# SCH_Octacon_Pots_Leds.net
KiCad netlist of a schematic drawn in EasyEDA
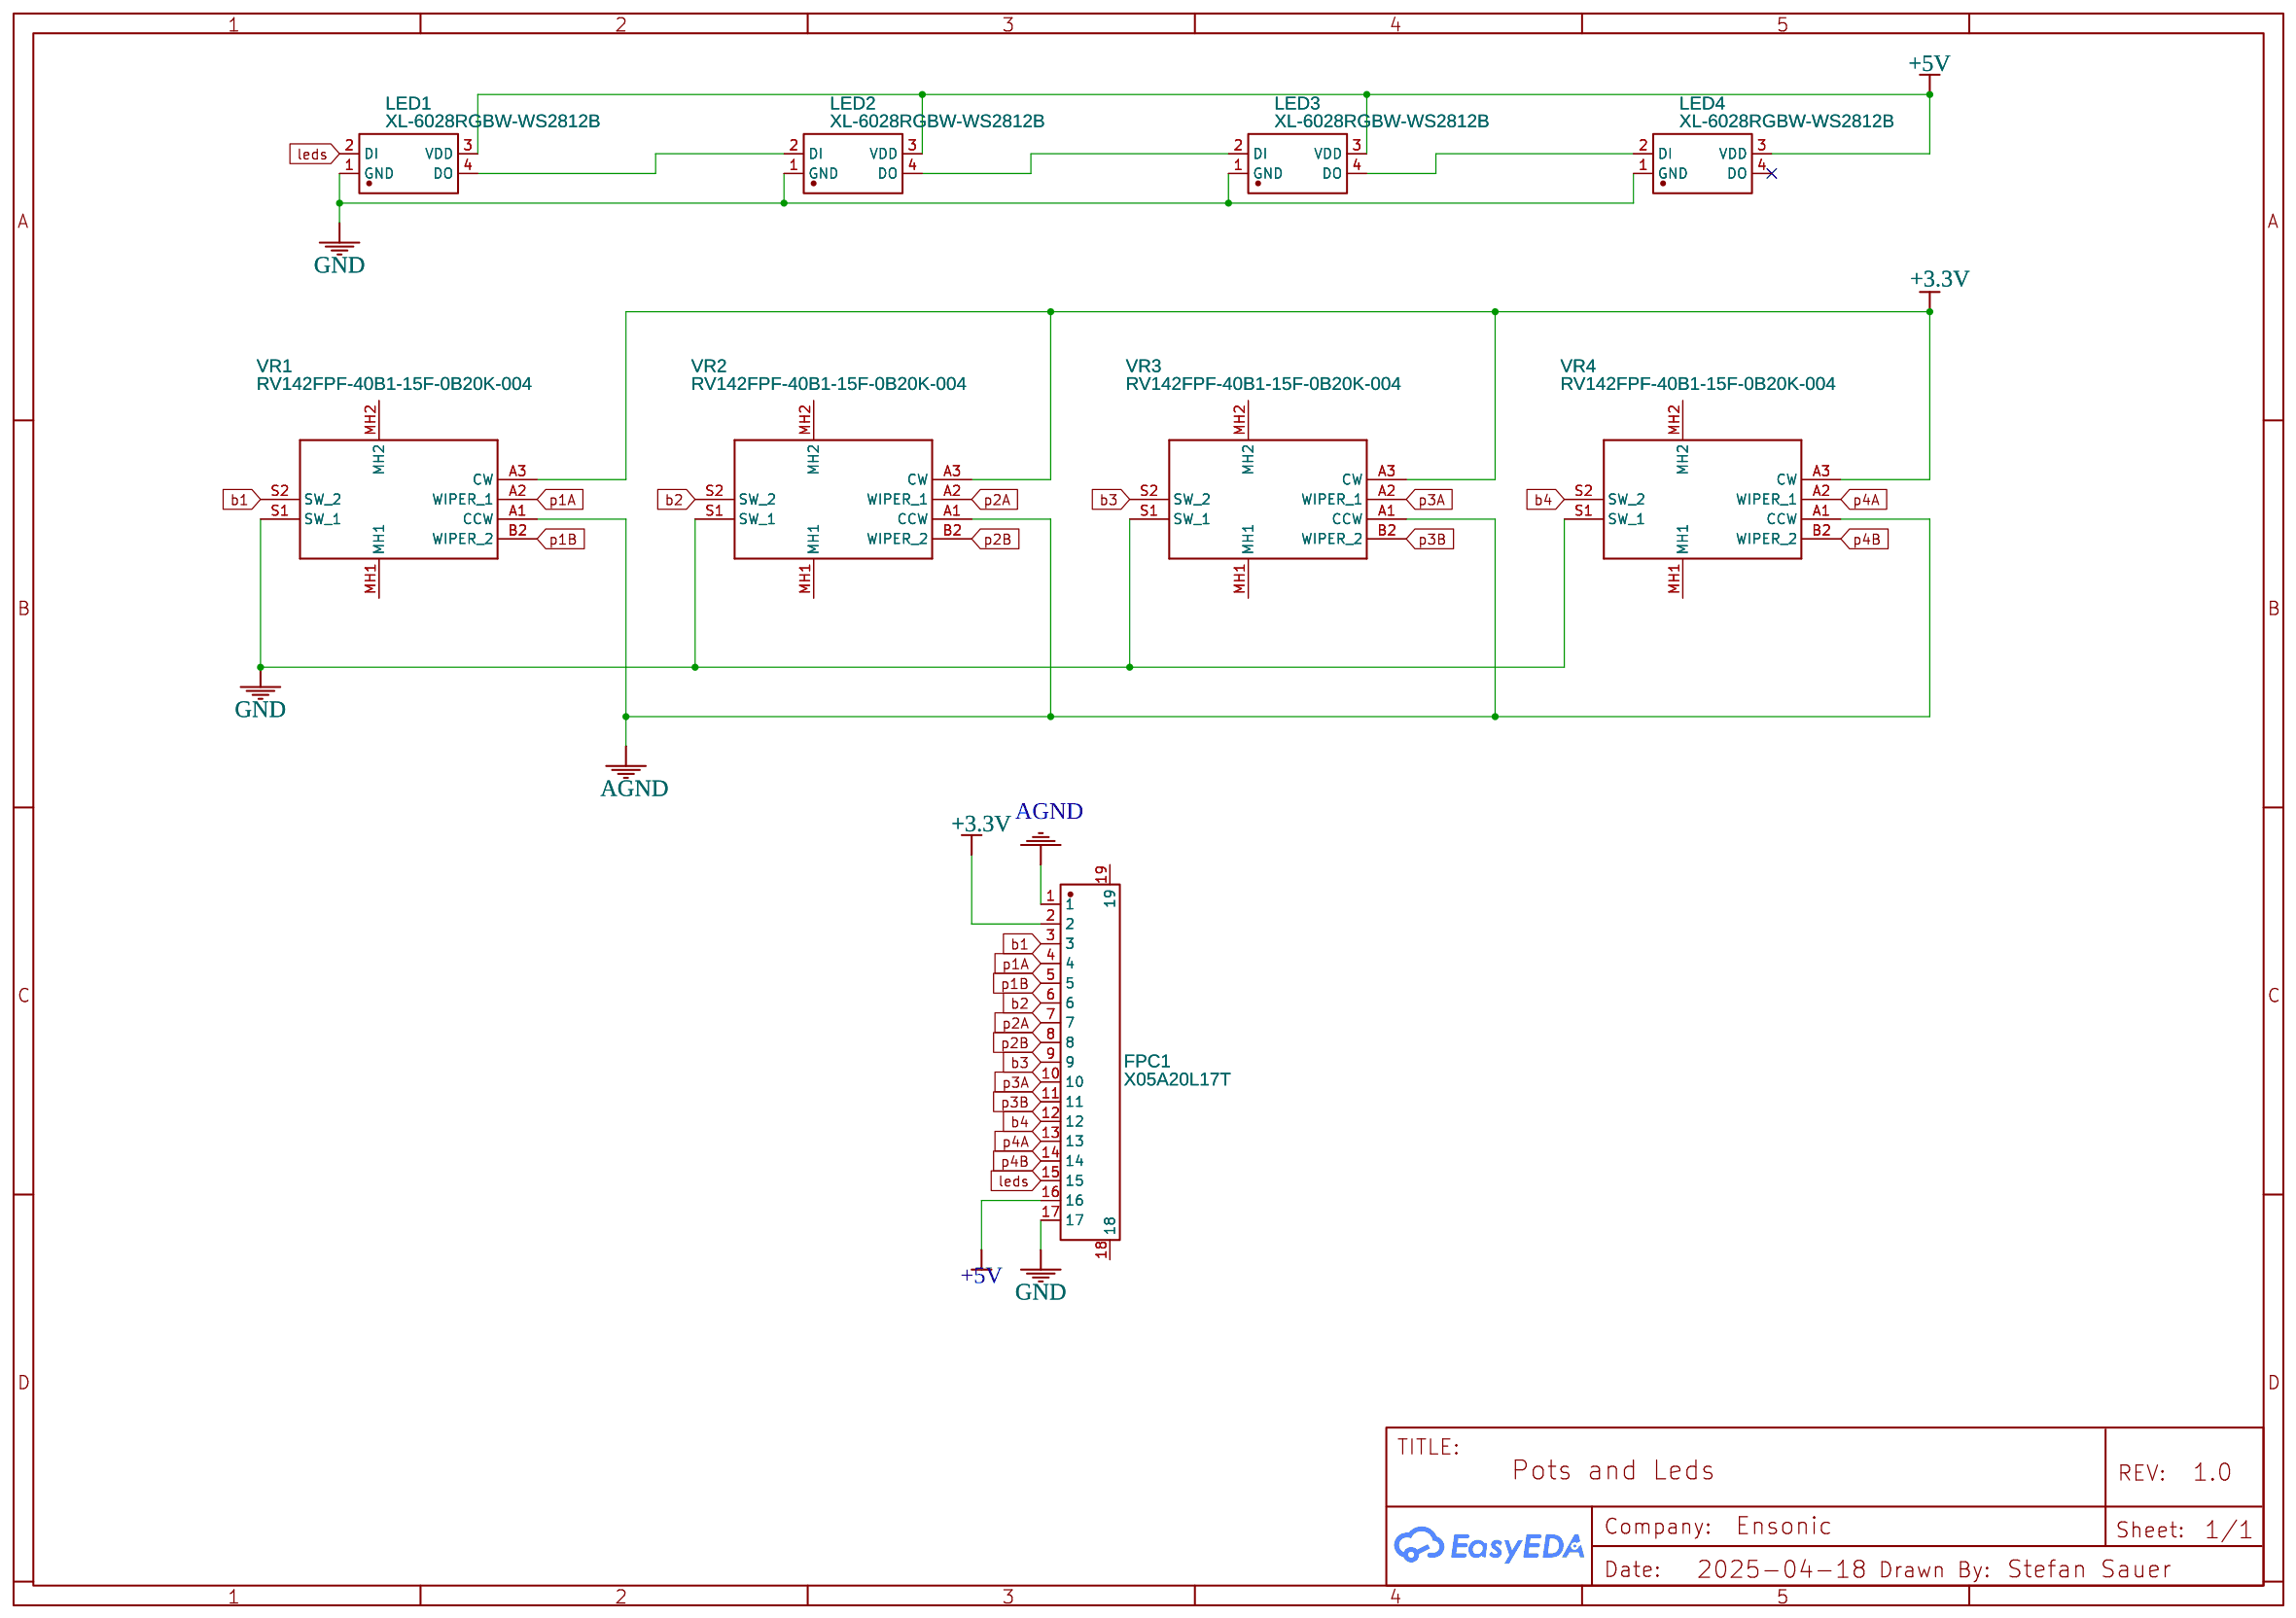
[diagram p0: schematic sheet]

(export (version "E")
  (design (tool "Eeschema 10.0.6"))
  (components
    (comp (ref "FPC1")
      (value "X05A20L17T")
      (fields (field (name "Manufacturer") "XKB Connection(中国星坤)"))
      (libsource (lib "") (part "X05A20L17T"))
    )
    (comp (ref "LED1")
      (value "XL-6028RGBW-WS2812B")
      (fields (field (name "Manufacturer") "XINGLIGHT(成兴光)"))
      (libsource (lib "") (part "XL-6028RGBW-WS2812B"))
    )
    (comp (ref "LED2")
      (value "XL-6028RGBW-WS2812B")
      (fields (field (name "Manufacturer") "XINGLIGHT(成兴光)"))
      (libsource (lib "") (part "XL-6028RGBW-WS2812B"))
    )
    (comp (ref "LED3")
      (value "XL-6028RGBW-WS2812B")
      (fields (field (name "Manufacturer") "XINGLIGHT(成兴光)"))
      (libsource (lib "") (part "XL-6028RGBW-WS2812B"))
    )
    (comp (ref "LED4")
      (value "XL-6028RGBW-WS2812B")
      (fields (field (name "Manufacturer") "XINGLIGHT(成兴光)"))
      (libsource (lib "") (part "XL-6028RGBW-WS2812B"))
    )
    (comp (ref "VR1")
      (value "RV142FPF-40B1-15F-0B20K-004")
      (libsource (lib "") (part "RV142FPF-40B1-15F-0B20K-004"))
    )
    (comp (ref "VR2")
      (value "RV142FPF-40B1-15F-0B20K-004")
      (libsource (lib "") (part "RV142FPF-40B1-15F-0B20K-004"))
    )
    (comp (ref "VR3")
      (value "RV142FPF-40B1-15F-0B20K-004")
      (libsource (lib "") (part "RV142FPF-40B1-15F-0B20K-004"))
    )
    (comp (ref "VR4")
      (value "RV142FPF-40B1-15F-0B20K-004")
      (libsource (lib "") (part "RV142FPF-40B1-15F-0B20K-004"))
    )
  )
  (nets
    (net (code "1") (name "+3.3V") (class "Default")
      (node (ref "FPC1") (pin "2") (pinfunction "2_2") (pintype "unspecified"))
      (node (ref "VR1") (pin "A3") (pinfunction "CW_A3") (pintype "bidirectional"))
      (node (ref "VR2") (pin "A3") (pinfunction "CW_A3") (pintype "bidirectional"))
      (node (ref "VR3") (pin "A3") (pinfunction "CW_A3") (pintype "bidirectional"))
      (node (ref "VR4") (pin "A3") (pinfunction "CW_A3") (pintype "bidirectional"))
    )
    (net (code "2") (name "+5V") (class "Default")
      (node (ref "FPC1") (pin "16") (pinfunction "16_16") (pintype "unspecified"))
      (node (ref "LED1") (pin "3") (pinfunction "VDD_3") (pintype "unspecified"))
      (node (ref "LED2") (pin "3") (pinfunction "VDD_3") (pintype "unspecified"))
      (node (ref "LED3") (pin "3") (pinfunction "VDD_3") (pintype "unspecified"))
      (node (ref "LED4") (pin "3") (pinfunction "VDD_3") (pintype "unspecified"))
    )
    (net (code "3") (name "AGND") (class "Default")
      (node (ref "FPC1") (pin "1") (pinfunction "1_1") (pintype "unspecified"))
      (node (ref "VR1") (pin "A1") (pinfunction "CCW_A1") (pintype "bidirectional"))
      (node (ref "VR2") (pin "A1") (pinfunction "CCW_A1") (pintype "bidirectional"))
      (node (ref "VR3") (pin "A1") (pinfunction "CCW_A1") (pintype "bidirectional"))
      (node (ref "VR4") (pin "A1") (pinfunction "CCW_A1") (pintype "bidirectional"))
    )
    (net (code "4") (name "GND") (class "Default")
      (node (ref "FPC1") (pin "17") (pinfunction "17_17") (pintype "unspecified"))
      (node (ref "LED1") (pin "1") (pinfunction "GND_1") (pintype "unspecified"))
      (node (ref "LED2") (pin "1") (pinfunction "GND_1") (pintype "unspecified"))
      (node (ref "LED3") (pin "1") (pinfunction "GND_1") (pintype "unspecified"))
      (node (ref "LED4") (pin "1") (pinfunction "GND_1") (pintype "unspecified"))
      (node (ref "VR1") (pin "S1") (pinfunction "SW_1_S1") (pintype "bidirectional"))
      (node (ref "VR2") (pin "S1") (pinfunction "SW_1_S1") (pintype "bidirectional"))
      (node (ref "VR3") (pin "S1") (pinfunction "SW_1_S1") (pintype "bidirectional"))
      (node (ref "VR4") (pin "S1") (pinfunction "SW_1_S1") (pintype "bidirectional"))
    )
    (net (code "5") (name "Net-(LED1-DO)") (class "Default")
      (node (ref "LED1") (pin "4") (pinfunction "DO_4") (pintype "unspecified"))
      (node (ref "LED2") (pin "2") (pinfunction "DI_2") (pintype "unspecified"))
    )
    (net (code "6") (name "Net-(LED2-DO)") (class "Default")
      (node (ref "LED2") (pin "4") (pinfunction "DO_4") (pintype "unspecified"))
      (node (ref "LED3") (pin "2") (pinfunction "DI_2") (pintype "unspecified"))
    )
    (net (code "7") (name "Net-(LED3-DO)") (class "Default")
      (node (ref "LED3") (pin "4") (pinfunction "DO_4") (pintype "unspecified"))
      (node (ref "LED4") (pin "2") (pinfunction "DI_2") (pintype "unspecified"))
    )
    (net (code "8") (name "b1") (class "Default")
      (node (ref "FPC1") (pin "3") (pinfunction "3_3") (pintype "unspecified"))
      (node (ref "VR1") (pin "S2") (pinfunction "SW_2_S2") (pintype "bidirectional"))
    )
    (net (code "9") (name "b2") (class "Default")
      (node (ref "FPC1") (pin "6") (pinfunction "6_6") (pintype "unspecified"))
      (node (ref "VR2") (pin "S2") (pinfunction "SW_2_S2") (pintype "bidirectional"))
    )
    (net (code "10") (name "b3") (class "Default")
      (node (ref "FPC1") (pin "9") (pinfunction "9_9") (pintype "unspecified"))
      (node (ref "VR3") (pin "S2") (pinfunction "SW_2_S2") (pintype "bidirectional"))
    )
    (net (code "11") (name "b4") (class "Default")
      (node (ref "FPC1") (pin "12") (pinfunction "12_12") (pintype "unspecified"))
      (node (ref "VR4") (pin "S2") (pinfunction "SW_2_S2") (pintype "bidirectional"))
    )
    (net (code "12") (name "leds") (class "Default")
      (node (ref "FPC1") (pin "15") (pinfunction "15_15") (pintype "unspecified"))
      (node (ref "LED1") (pin "2") (pinfunction "DI_2") (pintype "unspecified"))
    )
    (net (code "13") (name "p1A") (class "Default")
      (node (ref "FPC1") (pin "4") (pinfunction "4_4") (pintype "unspecified"))
      (node (ref "VR1") (pin "A2") (pinfunction "WIPER_1_A2") (pintype "bidirectional"))
    )
    (net (code "14") (name "p1B") (class "Default")
      (node (ref "FPC1") (pin "5") (pinfunction "5_5") (pintype "unspecified"))
      (node (ref "VR1") (pin "B2") (pinfunction "WIPER_2_B2") (pintype "bidirectional"))
    )
    (net (code "15") (name "p2A") (class "Default")
      (node (ref "FPC1") (pin "7") (pinfunction "7_7") (pintype "unspecified"))
      (node (ref "VR2") (pin "A2") (pinfunction "WIPER_1_A2") (pintype "bidirectional"))
    )
    (net (code "16") (name "p2B") (class "Default")
      (node (ref "FPC1") (pin "8") (pinfunction "8_8") (pintype "unspecified"))
      (node (ref "VR2") (pin "B2") (pinfunction "WIPER_2_B2") (pintype "bidirectional"))
    )
    (net (code "17") (name "p3A") (class "Default")
      (node (ref "FPC1") (pin "10") (pinfunction "10_10") (pintype "unspecified"))
      (node (ref "VR3") (pin "A2") (pinfunction "WIPER_1_A2") (pintype "bidirectional"))
    )
    (net (code "18") (name "p3B") (class "Default")
      (node (ref "FPC1") (pin "11") (pinfunction "11_11") (pintype "unspecified"))
      (node (ref "VR3") (pin "B2") (pinfunction "WIPER_2_B2") (pintype "bidirectional"))
    )
    (net (code "19") (name "p4A") (class "Default")
      (node (ref "FPC1") (pin "13") (pinfunction "13_13") (pintype "unspecified"))
      (node (ref "VR4") (pin "A2") (pinfunction "WIPER_1_A2") (pintype "bidirectional"))
    )
    (net (code "20") (name "p4B") (class "Default")
      (node (ref "FPC1") (pin "14") (pinfunction "14_14") (pintype "unspecified"))
      (node (ref "VR4") (pin "B2") (pinfunction "WIPER_2_B2") (pintype "bidirectional"))
    )
    (net (code "21") (name "unconnected-(FPC1-Pad18)") (class "Default")
      (node (ref "FPC1") (pin "18") (pinfunction "18_18") (pintype "unspecified"))
    )
    (net (code "22") (name "unconnected-(FPC1-Pad19)") (class "Default")
      (node (ref "FPC1") (pin "19") (pinfunction "19_19") (pintype "unspecified"))
    )
    (net (code "23") (name "unconnected-(LED4-DO-Pad4)") (class "Default")
      (node (ref "LED4") (pin "4") (pinfunction "DO_4") (pintype "unspecified+no_connect"))
    )
    (net (code "24") (name "unconnected-(VR1-PadMH1)") (class "Default")
      (node (ref "VR1") (pin "MH1") (pinfunction "MH1_MH1") (pintype "bidirectional"))
    )
    (net (code "25") (name "unconnected-(VR1-PadMH2)") (class "Default")
      (node (ref "VR1") (pin "MH2") (pinfunction "MH2_MH2") (pintype "bidirectional"))
    )
    (net (code "26") (name "unconnected-(VR2-PadMH1)") (class "Default")
      (node (ref "VR2") (pin "MH1") (pinfunction "MH1_MH1") (pintype "bidirectional"))
    )
    (net (code "27") (name "unconnected-(VR2-PadMH2)") (class "Default")
      (node (ref "VR2") (pin "MH2") (pinfunction "MH2_MH2") (pintype "bidirectional"))
    )
    (net (code "28") (name "unconnected-(VR3-PadMH1)") (class "Default")
      (node (ref "VR3") (pin "MH1") (pinfunction "MH1_MH1") (pintype "bidirectional"))
    )
    (net (code "29") (name "unconnected-(VR3-PadMH2)") (class "Default")
      (node (ref "VR3") (pin "MH2") (pinfunction "MH2_MH2") (pintype "bidirectional"))
    )
    (net (code "30") (name "unconnected-(VR4-PadMH1)") (class "Default")
      (node (ref "VR4") (pin "MH1") (pinfunction "MH1_MH1") (pintype "bidirectional"))
    )
    (net (code "31") (name "unconnected-(VR4-PadMH2)") (class "Default")
      (node (ref "VR4") (pin "MH2") (pinfunction "MH2_MH2") (pintype "bidirectional"))
    )
  )
)
